# fabscope.net
KiCad netlist of a schematic drawn in EAGLE
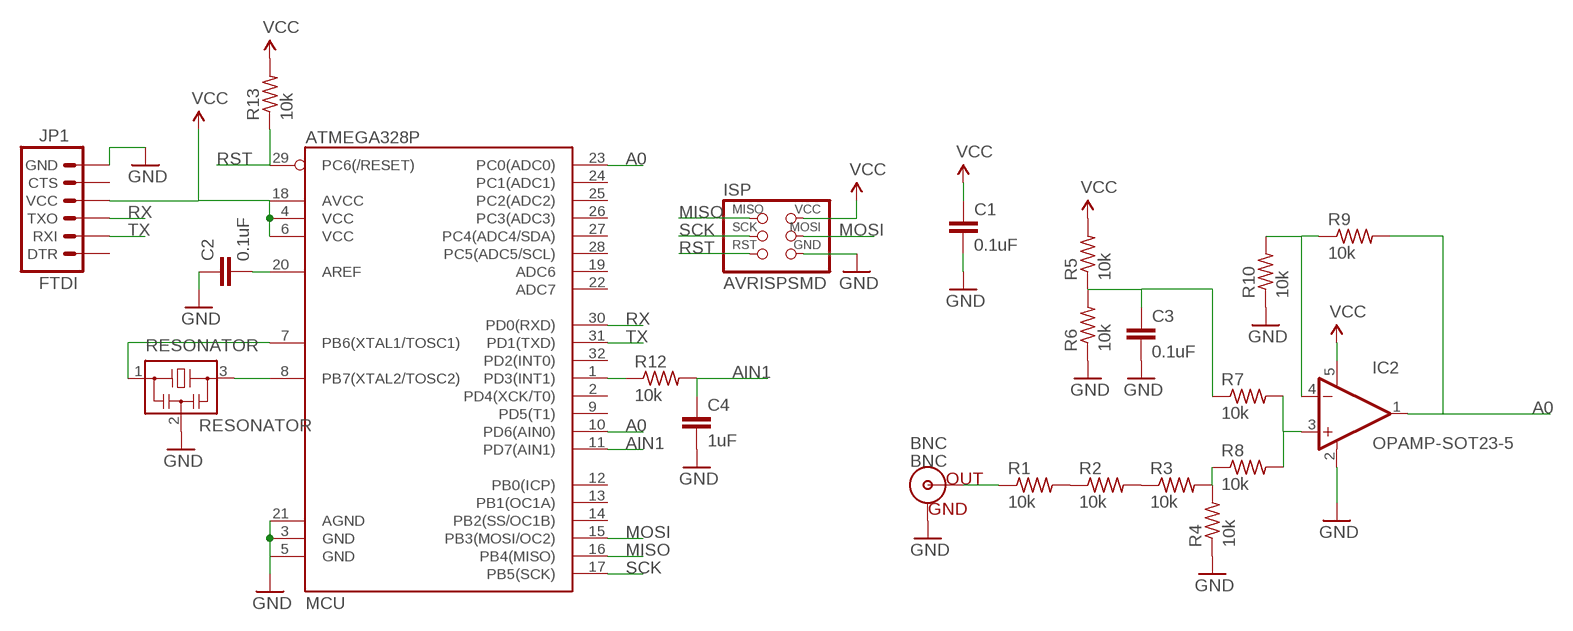
[diagram p0: schematic, sheet 1]

(export (version "E")
  (design (tool "Eeschema 10.0.6"))
  (components
    (comp (ref "BNC")
      (value "BNC")
      (footprint "eagle-import:BNC")
      (libsource (lib "eagle-import") (part "BNCPTH"))
    )
    (comp (ref "C1")
      (value "0.1uF")
      (footprint "eagle-import:C1206FAB")
      (libsource (lib "eagle-import") (part "CAPACITOR1206FAB"))
    )
    (comp (ref "C2")
      (value "0.1uF")
      (footprint "eagle-import:C1206FAB")
      (libsource (lib "eagle-import") (part "CAPACITOR1206FAB"))
    )
    (comp (ref "C3")
      (value "0.1uF")
      (footprint "eagle-import:C1206FAB")
      (libsource (lib "eagle-import") (part "CAPACITOR1206FAB"))
    )
    (comp (ref "C4")
      (value "1uF")
      (footprint "eagle-import:C1206FAB")
      (libsource (lib "eagle-import") (part "CAPACITOR1206FAB"))
    )
    (comp (ref "IC2")
      (value "OPAMP-SOT23-5")
      (footprint "eagle-import:SOT23-5")
      (libsource (lib "eagle-import") (part "OPAMP-SOT23-5"))
    )
    (comp (ref "ISP")
      (value "AVRISPSMD")
      (footprint "eagle-import:2X3SMD")
      (libsource (lib "eagle-import") (part "AVRISPSMD"))
    )
    (comp (ref "JP1")
      (value "FTDI")
      (footprint "eagle-import:FTDI-SMD")
      (libsource (lib "eagle-import") (part "FTDI-SMD"))
    )
    (comp (ref "MCU")
      (value "ATMEGA328P")
      (footprint "eagle-import:TQFP32-08")
      (libsource (lib "eagle-import") (part "ATMEGA328_SMT"))
    )
    (comp (ref "R1")
      (value "10k")
      (footprint "eagle-import:R1206FAB")
      (libsource (lib "eagle-import") (part "RES-US1206FAB"))
    )
    (comp (ref "R2")
      (value "10k")
      (footprint "eagle-import:R1206FAB")
      (libsource (lib "eagle-import") (part "RES-US1206FAB"))
    )
    (comp (ref "R3")
      (value "10k")
      (footprint "eagle-import:R1206FAB")
      (libsource (lib "eagle-import") (part "RES-US1206FAB"))
    )
    (comp (ref "R4")
      (value "10k")
      (footprint "eagle-import:R1206FAB")
      (libsource (lib "eagle-import") (part "RES-US1206FAB"))
    )
    (comp (ref "R5")
      (value "10k")
      (footprint "eagle-import:R1206FAB")
      (libsource (lib "eagle-import") (part "RES-US1206FAB"))
    )
    (comp (ref "R6")
      (value "10k")
      (footprint "eagle-import:R1206FAB")
      (libsource (lib "eagle-import") (part "RES-US1206FAB"))
    )
    (comp (ref "R7")
      (value "10k")
      (footprint "eagle-import:R1206FAB")
      (libsource (lib "eagle-import") (part "RES-US1206FAB"))
    )
    (comp (ref "R8")
      (value "10k")
      (footprint "eagle-import:R1206FAB")
      (libsource (lib "eagle-import") (part "RES-US1206FAB"))
    )
    (comp (ref "R9")
      (value "10k")
      (footprint "eagle-import:R1206FAB")
      (libsource (lib "eagle-import") (part "RES-US1206FAB"))
    )
    (comp (ref "R10")
      (value "10k")
      (footprint "eagle-import:R1206FAB")
      (libsource (lib "eagle-import") (part "RES-US1206FAB"))
    )
    (comp (ref "R12")
      (value "10k")
      (footprint "eagle-import:R1206FAB")
      (libsource (lib "eagle-import") (part "RES-US1206FAB"))
    )
    (comp (ref "R13")
      (value "10k")
      (footprint "eagle-import:R1206FAB")
      (libsource (lib "eagle-import") (part "RESISTOR1206FAB"))
    )
    (comp (ref "RESONATOR")
      (value "RESONATOR")
      (footprint "eagle-import:EFOBM")
      (libsource (lib "eagle-import") (part "RESONATOR"))
    )
  )
  (nets
    (net (code "1") (name "/A0") (class "Default")
      (node (ref "IC2") (pin "1") (pinfunction "OUT_1") (pintype "output"))
      (node (ref "MCU") (pin "10") (pinfunction "PD6(AIN0)_10") (pintype "bidirectional"))
      (node (ref "MCU") (pin "23") (pinfunction "PC0(ADC0)_23") (pintype "bidirectional"))
      (node (ref "R9") (pin "2") (pinfunction "2_2") (pintype "passive"))
    )
    (net (code "2") (name "/AIN1") (class "Default")
      (node (ref "C4") (pin "1") (pinfunction "1_1") (pintype "passive"))
      (node (ref "MCU") (pin "11") (pinfunction "PD7(AIN1)_11") (pintype "bidirectional"))
      (node (ref "R12") (pin "2") (pinfunction "2_2") (pintype "passive"))
    )
    (net (code "3") (name "/MISO") (class "Default")
      (node (ref "ISP") (pin "1") (pinfunction "MISO_1") (pintype "passive"))
      (node (ref "MCU") (pin "16") (pinfunction "PB4(MISO)_16") (pintype "bidirectional"))
    )
    (net (code "4") (name "/MOSI") (class "Default")
      (node (ref "ISP") (pin "4") (pinfunction "MOSI_4") (pintype "passive"))
      (node (ref "MCU") (pin "15") (pinfunction "PB3(MOSI/OC2)_15") (pintype "bidirectional"))
    )
    (net (code "5") (name "/RST") (class "Default")
      (node (ref "ISP") (pin "5") (pinfunction "RST_5") (pintype "passive"))
      (node (ref "MCU") (pin "29") (pinfunction "PC6(/RESET)_29") (pintype "bidirectional"))
      (node (ref "R13") (pin "1") (pinfunction "1_1") (pintype "passive"))
    )
    (net (code "6") (name "/RX") (class "Default")
      (node (ref "JP1") (pin "3") (pinfunction "TXO_3") (pintype "passive"))
      (node (ref "MCU") (pin "30") (pinfunction "PD0(RXD)_30") (pintype "bidirectional"))
    )
    (net (code "7") (name "/SCK") (class "Default")
      (node (ref "ISP") (pin "3") (pinfunction "SCK_3") (pintype "passive"))
      (node (ref "MCU") (pin "17") (pinfunction "PB5(SCK)_17") (pintype "bidirectional"))
    )
    (net (code "8") (name "/TX") (class "Default")
      (node (ref "JP1") (pin "2") (pinfunction "RXI_2") (pintype "passive"))
      (node (ref "MCU") (pin "31") (pinfunction "PD1(TXD)_31") (pintype "bidirectional"))
    )
    (net (code "9") (name "GND") (class "Default")
      (node (ref "BNC") (pin "GND") (pinfunction "GND_GND") (pintype "bidirectional"))
      (node (ref "C1") (pin "2") (pinfunction "2_2") (pintype "passive"))
      (node (ref "C2") (pin "1") (pinfunction "1_1") (pintype "passive"))
      (node (ref "C3") (pin "2") (pinfunction "2_2") (pintype "passive"))
      (node (ref "C4") (pin "2") (pinfunction "2_2") (pintype "passive"))
      (node (ref "IC2") (pin "2") (pinfunction "V-_2") (pintype "power_in"))
      (node (ref "ISP") (pin "6") (pinfunction "GND_6") (pintype "passive"))
      (node (ref "JP1") (pin "6") (pinfunction "GND_6") (pintype "passive"))
      (node (ref "MCU") (pin "21") (pinfunction "AGND_21") (pintype "bidirectional"))
      (node (ref "MCU") (pin "3") (pinfunction "GND_3") (pintype "bidirectional"))
      (node (ref "MCU") (pin "5") (pinfunction "GND_5") (pintype "bidirectional"))
      (node (ref "R10") (pin "1") (pinfunction "1_1") (pintype "passive"))
      (node (ref "R4") (pin "1") (pinfunction "1_1") (pintype "passive"))
      (node (ref "R6") (pin "1") (pinfunction "1_1") (pintype "passive"))
      (node (ref "RESONATOR") (pin "2") (pinfunction "2_2") (pintype "passive"))
    )
    (net (code "10") (name "Net-(BNC-OUT)") (class "Default")
      (node (ref "BNC") (pin "S") (pinfunction "OUT_S") (pintype "bidirectional"))
      (node (ref "R1") (pin "1") (pinfunction "1_1") (pintype "passive"))
    )
    (net (code "11") (name "Net-(C3-Pad1)") (class "Default")
      (node (ref "C3") (pin "1") (pinfunction "1_1") (pintype "passive"))
      (node (ref "R5") (pin "1") (pinfunction "1_1") (pintype "passive"))
      (node (ref "R6") (pin "2") (pinfunction "2_2") (pintype "passive"))
      (node (ref "R7") (pin "1") (pinfunction "1_1") (pintype "passive"))
    )
    (net (code "12") (name "Net-(IC2-+IN)") (class "Default")
      (node (ref "IC2") (pin "3") (pinfunction "+IN_3") (pintype "input"))
      (node (ref "R7") (pin "2") (pinfunction "2_2") (pintype "passive"))
      (node (ref "R8") (pin "2") (pinfunction "2_2") (pintype "passive"))
    )
    (net (code "13") (name "Net-(IC2--IN)") (class "Default")
      (node (ref "IC2") (pin "4") (pinfunction "-IN_4") (pintype "input"))
      (node (ref "R10") (pin "2") (pinfunction "2_2") (pintype "passive"))
      (node (ref "R9") (pin "1") (pinfunction "1_1") (pintype "passive"))
    )
    (net (code "14") (name "Net-(MCU-AREF)") (class "Default")
      (node (ref "C2") (pin "2") (pinfunction "2_2") (pintype "passive"))
      (node (ref "MCU") (pin "20") (pinfunction "AREF_20") (pintype "bidirectional"))
    )
    (net (code "15") (name "Net-(MCU-PB6(XTAL1{slash}TOSC1))") (class "Default")
      (node (ref "MCU") (pin "7") (pinfunction "PB6(XTAL1/TOSC1)_7") (pintype "bidirectional"))
      (node (ref "RESONATOR") (pin "1") (pinfunction "1_1") (pintype "passive"))
    )
    (net (code "16") (name "Net-(MCU-PB7(XTAL2{slash}TOSC2))") (class "Default")
      (node (ref "MCU") (pin "8") (pinfunction "PB7(XTAL2/TOSC2)_8") (pintype "bidirectional"))
      (node (ref "RESONATOR") (pin "3") (pinfunction "3_3") (pintype "passive"))
    )
    (net (code "17") (name "Net-(MCU-PD3(INT1))") (class "Default")
      (node (ref "MCU") (pin "1") (pinfunction "PD3(INT1)_1") (pintype "bidirectional"))
      (node (ref "R12") (pin "1") (pinfunction "1_1") (pintype "passive"))
    )
    (net (code "18") (name "Net-(R1-Pad2)") (class "Default")
      (node (ref "R1") (pin "2") (pinfunction "2_2") (pintype "passive"))
      (node (ref "R2") (pin "1") (pinfunction "1_1") (pintype "passive"))
    )
    (net (code "19") (name "Net-(R2-Pad2)") (class "Default")
      (node (ref "R2") (pin "2") (pinfunction "2_2") (pintype "passive"))
      (node (ref "R3") (pin "1") (pinfunction "1_1") (pintype "passive"))
    )
    (net (code "20") (name "Net-(R3-Pad2)") (class "Default")
      (node (ref "R3") (pin "2") (pinfunction "2_2") (pintype "passive"))
      (node (ref "R4") (pin "2") (pinfunction "2_2") (pintype "passive"))
      (node (ref "R8") (pin "1") (pinfunction "1_1") (pintype "passive"))
    )
    (net (code "21") (name "VCC") (class "Default")
      (node (ref "C1") (pin "1") (pinfunction "1_1") (pintype "passive"))
      (node (ref "IC2") (pin "5") (pinfunction "V+_5") (pintype "power_in"))
      (node (ref "ISP") (pin "2") (pinfunction "VCC_2") (pintype "passive"))
      (node (ref "JP1") (pin "4") (pinfunction "VCC_4") (pintype "passive"))
      (node (ref "MCU") (pin "18") (pinfunction "AVCC_18") (pintype "bidirectional"))
      (node (ref "MCU") (pin "4") (pinfunction "VCC_4") (pintype "bidirectional"))
      (node (ref "MCU") (pin "6") (pinfunction "VCC_6") (pintype "bidirectional"))
      (node (ref "R13") (pin "2") (pinfunction "2_2") (pintype "passive"))
      (node (ref "R5") (pin "2") (pinfunction "2_2") (pintype "passive"))
    )
    (net (code "22") (name "unconnected-(JP1-CTS-Pad5)") (class "Default")
      (node (ref "JP1") (pin "5") (pinfunction "CTS_5") (pintype "passive"))
    )
    (net (code "23") (name "unconnected-(JP1-DTR-Pad1)") (class "Default")
      (node (ref "JP1") (pin "1") (pinfunction "DTR_1") (pintype "passive"))
    )
    (net (code "24") (name "unconnected-(MCU-ADC6-Pad19)") (class "Default")
      (node (ref "MCU") (pin "19") (pinfunction "ADC6_19") (pintype "bidirectional"))
    )
    (net (code "25") (name "unconnected-(MCU-ADC7-Pad22)") (class "Default")
      (node (ref "MCU") (pin "22") (pinfunction "ADC7_22") (pintype "bidirectional"))
    )
    (net (code "26") (name "unconnected-(MCU-PB0(ICP)-Pad12)") (class "Default")
      (node (ref "MCU") (pin "12") (pinfunction "PB0(ICP)_12") (pintype "bidirectional"))
    )
    (net (code "27") (name "unconnected-(MCU-PB1(OC1A)-Pad13)") (class "Default")
      (node (ref "MCU") (pin "13") (pinfunction "PB1(OC1A)_13") (pintype "bidirectional"))
    )
    (net (code "28") (name "unconnected-(MCU-PB2(SS{slash}OC1B)-Pad14)") (class "Default")
      (node (ref "MCU") (pin "14") (pinfunction "PB2(SS/OC1B)_14") (pintype "bidirectional"))
    )
    (net (code "29") (name "unconnected-(MCU-PC1(ADC1)-Pad24)") (class "Default")
      (node (ref "MCU") (pin "24") (pinfunction "PC1(ADC1)_24") (pintype "bidirectional"))
    )
    (net (code "30") (name "unconnected-(MCU-PC2(ADC2)-Pad25)") (class "Default")
      (node (ref "MCU") (pin "25") (pinfunction "PC2(ADC2)_25") (pintype "bidirectional"))
    )
    (net (code "31") (name "unconnected-(MCU-PC3(ADC3)-Pad26)") (class "Default")
      (node (ref "MCU") (pin "26") (pinfunction "PC3(ADC3)_26") (pintype "bidirectional"))
    )
    (net (code "32") (name "unconnected-(MCU-PC4(ADC4{slash}SDA)-Pad27)") (class "Default")
      (node (ref "MCU") (pin "27") (pinfunction "PC4(ADC4/SDA)_27") (pintype "bidirectional"))
    )
    (net (code "33") (name "unconnected-(MCU-PC5(ADC5{slash}SCL)-Pad28)") (class "Default")
      (node (ref "MCU") (pin "28") (pinfunction "PC5(ADC5/SCL)_28") (pintype "bidirectional"))
    )
    (net (code "34") (name "unconnected-(MCU-PD2(INT0)-Pad32)") (class "Default")
      (node (ref "MCU") (pin "32") (pinfunction "PD2(INT0)_32") (pintype "bidirectional"))
    )
    (net (code "35") (name "unconnected-(MCU-PD4(XCK{slash}T0)-Pad2)") (class "Default")
      (node (ref "MCU") (pin "2") (pinfunction "PD4(XCK/T0)_2") (pintype "bidirectional"))
    )
    (net (code "36") (name "unconnected-(MCU-PD5(T1)-Pad9)") (class "Default")
      (node (ref "MCU") (pin "9") (pinfunction "PD5(T1)_9") (pintype "bidirectional"))
    )
  )
)
